# control-10.net
KiCad netlist of a schematic drawn in EAGLE
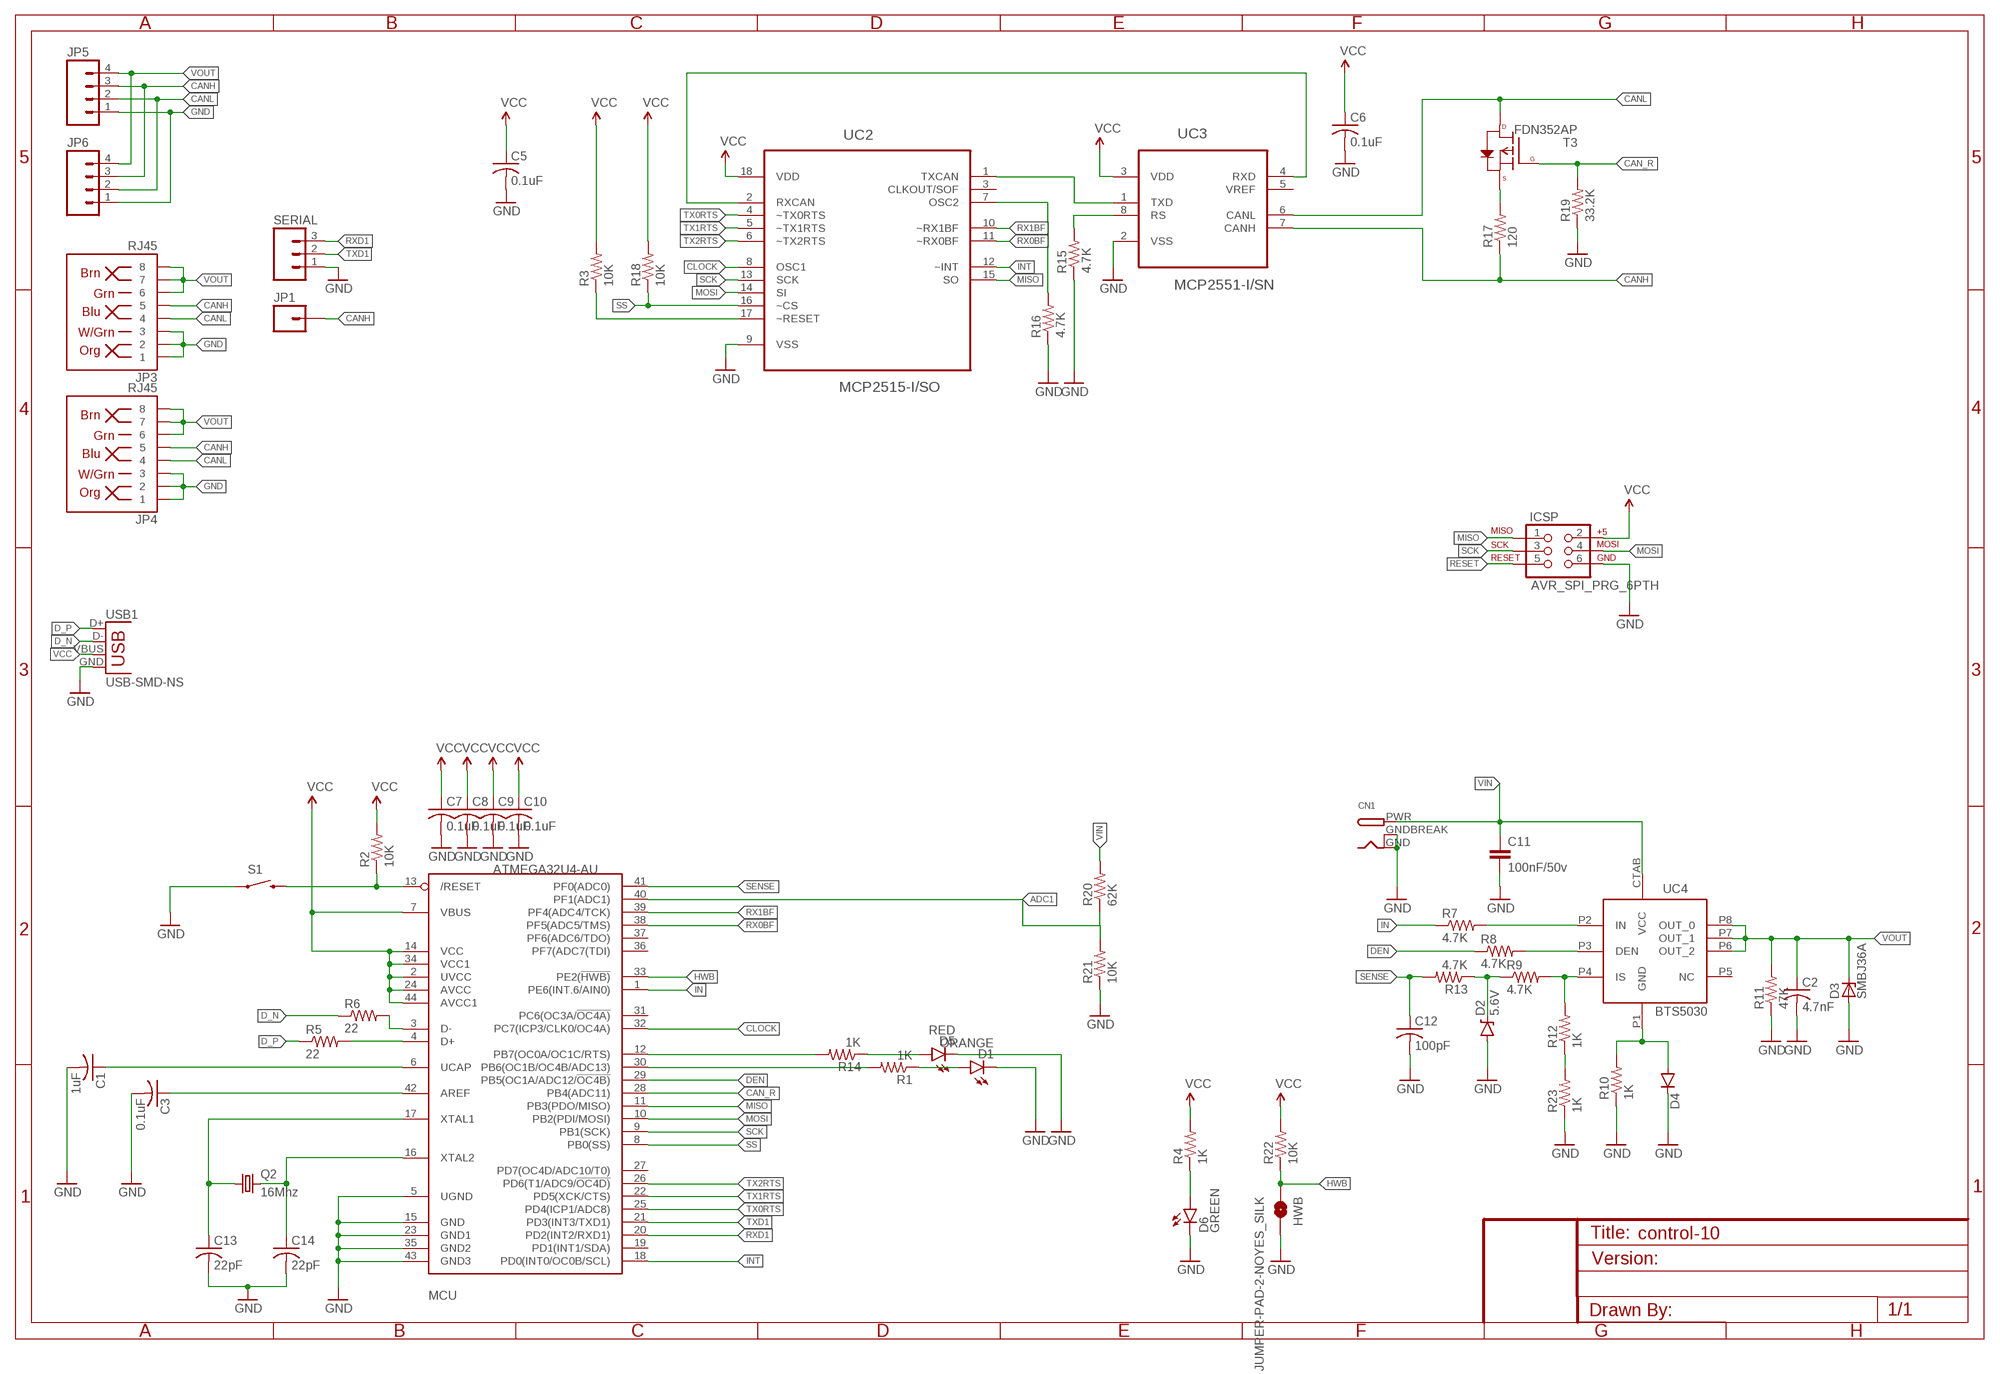
[diagram p0: schematic, sheet 1]

(export (version "E")
  (design (tool "Eeschema 10.0.6"))
  (components
    (comp (ref "C1")
      (value "1uF")
      (footprint "eagle-import:C0805")
      (libsource (lib "eagle-import") (part "C-USC0805"))
    )
    (comp (ref "C2")
      (value "4.7nF")
      (footprint "eagle-import:C0805")
      (libsource (lib "eagle-import") (part "C-USC0805"))
    )
    (comp (ref "C3")
      (value "0.1uF")
      (footprint "eagle-import:C0603")
      (libsource (lib "eagle-import") (part "C-USC0603"))
    )
    (comp (ref "C5")
      (value "0.1uF")
      (footprint "eagle-import:C0603")
      (libsource (lib "eagle-import") (part "C-USC0603"))
    )
    (comp (ref "C6")
      (value "0.1uF")
      (footprint "eagle-import:C0603")
      (libsource (lib "eagle-import") (part "C-USC0603"))
    )
    (comp (ref "C7")
      (value "0.1uF")
      (footprint "eagle-import:C0603")
      (libsource (lib "eagle-import") (part "C-USC0603"))
    )
    (comp (ref "C8")
      (value "0.1uF")
      (footprint "eagle-import:C0603")
      (libsource (lib "eagle-import") (part "C-USC0603"))
    )
    (comp (ref "C9")
      (value "0.1uF")
      (footprint "eagle-import:C0603")
      (libsource (lib "eagle-import") (part "C-USC0603"))
    )
    (comp (ref "C10")
      (value "0.1uF")
      (footprint "eagle-import:C0603")
      (libsource (lib "eagle-import") (part "C-USC0603"))
    )
    (comp (ref "C11")
      (value "100nF/50v")
      (footprint "eagle-import:0805")
      (libsource (lib "eagle-import") (part "CAP0805"))
    )
    (comp (ref "C12")
      (value "100pF")
      (footprint "eagle-import:C0805")
      (libsource (lib "eagle-import") (part "C-USC0805"))
    )
    (comp (ref "C13")
      (value "22pF")
      (footprint "eagle-import:C0805")
      (libsource (lib "eagle-import") (part "C-USC0805"))
    )
    (comp (ref "C14")
      (value "22pF")
      (footprint "eagle-import:C0805")
      (libsource (lib "eagle-import") (part "C-USC0805"))
    )
    (comp (ref "CN1")
      (value "DCBARRELPTH")
      (footprint "eagle-import:DCJACK_2MM_PTH")
      (libsource (lib "eagle-import") (part "DCBARRELPTH"))
    )
    (comp (ref "D1")
      (value "ORANGE")
      (footprint "eagle-import:LED-1206")
      (libsource (lib "eagle-import") (part "LED1206"))
    )
    (comp (ref "D2")
      (value "5.6V")
      (footprint "eagle-import:SOD-323")
      (libsource (lib "eagle-import") (part "DIODE-ZENER5.6V"))
    )
    (comp (ref "D3")
      (value "SMBJ36A")
      (footprint "eagle-import:SMB")
      (libsource (lib "eagle-import") (part "ZENER-DIODESMB"))
    )
    (comp (ref "D4")
      (value "DIODESMA")
      (footprint "eagle-import:SMA-DIODE")
      (libsource (lib "eagle-import") (part "DIODESMA"))
    )
    (comp (ref "D5")
      (value "RED")
      (footprint "eagle-import:LED-1206")
      (libsource (lib "eagle-import") (part "LED1206"))
    )
    (comp (ref "D6")
      (value "GREEN")
      (footprint "eagle-import:LED-1206")
      (libsource (lib "eagle-import") (part "LED1206"))
    )
    (comp (ref "HWB")
      (value "JUMPER-PAD-2-NOYES_SILK")
      (footprint "eagle-import:PAD-JUMPER-2-NO_YES_SILK")
      (libsource (lib "eagle-import") (part "JUMPER-PAD-2-NOYES_SILK"))
    )
    (comp (ref "ICSP")
      (value "AVR_SPI_PRG_6PTH")
      (footprint "eagle-import:2X3")
      (libsource (lib "eagle-import") (part "AVR_SPI_PRG_6PTH"))
    )
    (comp (ref "JP1")
      (value "M01NOSILK-KIT")
      (footprint "eagle-import:1X01NS-KIT")
      (libsource (lib "eagle-import") (part "M01NOSILK-KIT"))
    )
    (comp (ref "JP3")
      (value "RJ45")
      (footprint "eagle-import:RJ45-8")
      (libsource (lib "eagle-import") (part "RJ45-8PTH"))
    )
    (comp (ref "JP4")
      (value "RJ45")
      (footprint "eagle-import:RJ45-8")
      (libsource (lib "eagle-import") (part "RJ45-8PTH"))
    )
    (comp (ref "JP5")
      (value "M04SCREW")
      (footprint "eagle-import:SCREWTERMINAL-3.5MM-4")
      (libsource (lib "eagle-import") (part "M04SCREW"))
    )
    (comp (ref "JP6")
      (value "M04SCREW")
      (footprint "eagle-import:SCREWTERMINAL-3.5MM-4")
      (libsource (lib "eagle-import") (part "M04SCREW"))
    )
    (comp (ref "MCU")
      (value "ATMEGA32U4-AU")
      (footprint "eagle-import:TQFP44")
      (libsource (lib "eagle-import") (part "ATMEGA32U4-AU"))
    )
    (comp (ref "Q2")
      (value "16Mhz")
      (footprint "eagle-import:HC49UP")
      (libsource (lib "eagle-import") (part "CRYSTALSMD"))
    )
    (comp (ref "R1")
      (value "1K")
      (footprint "eagle-import:0805")
      (libsource (lib "eagle-import") (part "RESISTOR0805-RES"))
    )
    (comp (ref "R2")
      (value "10K")
      (footprint "eagle-import:M0805")
      (libsource (lib "eagle-import") (part "R-US_M0805"))
    )
    (comp (ref "R3")
      (value "10K")
      (footprint "eagle-import:M0805")
      (libsource (lib "eagle-import") (part "R-US_M0805"))
    )
    (comp (ref "R4")
      (value "1K")
      (footprint "eagle-import:0805")
      (libsource (lib "eagle-import") (part "RESISTOR0805-RES"))
    )
    (comp (ref "R5")
      (value "22")
      (footprint "eagle-import:M0805")
      (libsource (lib "eagle-import") (part "R-US_M0805"))
    )
    (comp (ref "R6")
      (value "22")
      (footprint "eagle-import:M0805")
      (libsource (lib "eagle-import") (part "R-US_M0805"))
    )
    (comp (ref "R7")
      (value "4.7K")
      (footprint "eagle-import:M0805")
      (libsource (lib "eagle-import") (part "R-US_M0805"))
    )
    (comp (ref "R8")
      (value "4.7K")
      (footprint "eagle-import:M0805")
      (libsource (lib "eagle-import") (part "R-US_M0805"))
    )
    (comp (ref "R9")
      (value "4.7K")
      (footprint "eagle-import:M0805")
      (libsource (lib "eagle-import") (part "R-US_M0805"))
    )
    (comp (ref "R10")
      (value "1K")
      (footprint "eagle-import:M0805")
      (libsource (lib "eagle-import") (part "R-US_M0805"))
    )
    (comp (ref "R11")
      (value "47K")
      (footprint "eagle-import:M0805")
      (libsource (lib "eagle-import") (part "R-US_M0805"))
    )
    (comp (ref "R12")
      (value "1K")
      (footprint "eagle-import:M0805")
      (libsource (lib "eagle-import") (part "R-US_M0805"))
    )
    (comp (ref "R13")
      (value "4.7K")
      (footprint "eagle-import:M0805")
      (libsource (lib "eagle-import") (part "R-US_M0805"))
    )
    (comp (ref "R14")
      (value "1K")
      (footprint "eagle-import:0805")
      (libsource (lib "eagle-import") (part "RESISTOR0805-RES"))
    )
    (comp (ref "R15")
      (value "4.7K")
      (footprint "eagle-import:M0805")
      (libsource (lib "eagle-import") (part "R-US_M0805"))
    )
    (comp (ref "R16")
      (value "4.7K")
      (footprint "eagle-import:M0805")
      (libsource (lib "eagle-import") (part "R-US_M0805"))
    )
    (comp (ref "R17")
      (value "120")
      (footprint "eagle-import:M0805")
      (libsource (lib "eagle-import") (part "R-US_M0805"))
    )
    (comp (ref "R18")
      (value "10K")
      (footprint "eagle-import:M0805")
      (libsource (lib "eagle-import") (part "R-US_M0805"))
    )
    (comp (ref "R19")
      (value "33.2K")
      (footprint "eagle-import:M0805")
      (libsource (lib "eagle-import") (part "R-US_M0805"))
    )
    (comp (ref "R20")
      (value "62K")
      (footprint "eagle-import:M0805")
      (libsource (lib "eagle-import") (part "R-US_M0805"))
    )
    (comp (ref "R21")
      (value "10K")
      (footprint "eagle-import:M0805")
      (libsource (lib "eagle-import") (part "R-US_M0805"))
    )
    (comp (ref "R22")
      (value "10K")
      (footprint "eagle-import:M0805")
      (libsource (lib "eagle-import") (part "R-US_M0805"))
    )
    (comp (ref "R23")
      (value "1K")
      (footprint "eagle-import:M0805")
      (libsource (lib "eagle-import") (part "R-US_M0805"))
    )
    (comp (ref "S1")
      (value "SWITCH-MOMENTARY-2SMD-1101NE")
      (footprint "eagle-import:TACTILE-SWITCH-1101NE")
      (libsource (lib "eagle-import") (part "SWITCH-MOMENTARY-2SMD-1101NE"))
    )
    (comp (ref "SERIAL")
      (value "M03PTH")
      (footprint "eagle-import:1X03")
      (libsource (lib "eagle-import") (part "M03PTH"))
    )
    (comp (ref "T3")
      (value "FDN352AP")
      (footprint "eagle-import:SOT23-3")
      (libsource (lib "eagle-import") (part "P-CHANNEL-MOSFET"))
    )
    (comp (ref "UC2")
      (value "MCP2515-I/SO")
      (footprint "eagle-import:SOIC127P1034X264-18N")
      (libsource (lib "eagle-import") (part "MCP2515-I/SO"))
    )
    (comp (ref "UC3")
      (value "MCP2551-I/SN")
      (footprint "eagle-import:SOIC127P600X175-8N")
      (libsource (lib "eagle-import") (part "MCP2551-I/SN"))
    )
    (comp (ref "UC4")
      (value "BTS5030")
      (footprint "eagle-import:PG-DSO-8-43")
      (libsource (lib "eagle-import") (part "BTS5030"))
    )
    (comp (ref "USB1")
      (value "USB-SMD-NS")
      (footprint "eagle-import:USB-MINIB-NOSTOP")
      (libsource (lib "eagle-import") (part "USB-SMD-NS"))
    )
  )
  (nets
    (net (code "1") (name "ADC1") (class "Default")
      (node (ref "MCU") (pin "40") (pinfunction "PF1(ADC1)_40") (pintype "bidirectional"))
      (node (ref "R20") (pin "1") (pinfunction "1_1") (pintype "passive"))
      (node (ref "R21") (pin "2") (pinfunction "2_2") (pintype "passive"))
    )
    (net (code "2") (name "CANH") (class "Default")
      (node (ref "JP1") (pin "1") (pinfunction "1_1") (pintype "passive"))
      (node (ref "JP3") (pin "5") (pinfunction "5_5") (pintype "bidirectional"))
      (node (ref "JP4") (pin "5") (pinfunction "5_5") (pintype "bidirectional"))
      (node (ref "JP5") (pin "3") (pinfunction "3_3") (pintype "passive"))
      (node (ref "JP6") (pin "3") (pinfunction "3_3") (pintype "passive"))
      (node (ref "R17") (pin "1") (pinfunction "1_1") (pintype "passive"))
      (node (ref "UC3") (pin "7") (pinfunction "CANH_7") (pintype "bidirectional"))
    )
    (net (code "3") (name "CANL") (class "Default")
      (node (ref "JP3") (pin "4") (pinfunction "4_4") (pintype "bidirectional"))
      (node (ref "JP4") (pin "4") (pinfunction "4_4") (pintype "bidirectional"))
      (node (ref "JP5") (pin "2") (pinfunction "2_2") (pintype "passive"))
      (node (ref "JP6") (pin "2") (pinfunction "2_2") (pintype "passive"))
      (node (ref "T3") (pin "3") (pinfunction "D_3") (pintype "passive"))
      (node (ref "UC3") (pin "6") (pinfunction "CANL_6") (pintype "bidirectional"))
    )
    (net (code "4") (name "CAN_R") (class "Default")
      (node (ref "MCU") (pin "28") (pinfunction "PB4(ADC11)_28") (pintype "bidirectional"))
      (node (ref "R19") (pin "2") (pinfunction "2_2") (pintype "passive"))
      (node (ref "T3") (pin "1") (pinfunction "G_1") (pintype "passive"))
    )
    (net (code "5") (name "CLOCK") (class "Default")
      (node (ref "MCU") (pin "32") (pinfunction "PC7(ICP3/CLK0/OC4A)_32") (pintype "bidirectional"))
      (node (ref "UC2") (pin "8") (pinfunction "OSC1_8") (pintype "input"))
    )
    (net (code "6") (name "DEN") (class "Default")
      (node (ref "MCU") (pin "29") (pinfunction "PB5(OC1A/ADC12/~{OC4B})_29") (pintype "bidirectional"))
      (node (ref "R8") (pin "1") (pinfunction "1_1") (pintype "passive"))
    )
    (net (code "7") (name "D_N") (class "Default")
      (node (ref "R6") (pin "1") (pinfunction "1_1") (pintype "passive"))
      (node (ref "USB1") (pin "D-") (pinfunction "D-_D-") (pintype "bidirectional"))
    )
    (net (code "8") (name "D_P") (class "Default")
      (node (ref "R5") (pin "1") (pinfunction "1_1") (pintype "passive"))
      (node (ref "USB1") (pin "D+") (pinfunction "D+_D+") (pintype "bidirectional"))
    )
    (net (code "9") (name "GND") (class "Default")
      (node (ref "C1") (pin "2") (pinfunction "2_2") (pintype "passive"))
      (node (ref "C10") (pin "2") (pinfunction "2_2") (pintype "passive"))
      (node (ref "C11") (pin "2") (pinfunction "2_2") (pintype "passive"))
      (node (ref "C12") (pin "2") (pinfunction "2_2") (pintype "passive"))
      (node (ref "C13") (pin "2") (pinfunction "2_2") (pintype "passive"))
      (node (ref "C14") (pin "2") (pinfunction "2_2") (pintype "passive"))
      (node (ref "C2") (pin "2") (pinfunction "2_2") (pintype "passive"))
      (node (ref "C3") (pin "2") (pinfunction "2_2") (pintype "passive"))
      (node (ref "C5") (pin "2") (pinfunction "2_2") (pintype "passive"))
      (node (ref "C6") (pin "2") (pinfunction "2_2") (pintype "passive"))
      (node (ref "C7") (pin "2") (pinfunction "2_2") (pintype "passive"))
      (node (ref "C8") (pin "2") (pinfunction "2_2") (pintype "passive"))
      (node (ref "C9") (pin "2") (pinfunction "2_2") (pintype "passive"))
      (node (ref "CN1") (pin "GND") (pinfunction "GND_GND") (pintype "power_in"))
      (node (ref "CN1") (pin "GNDBREAK") (pinfunction "GNDBREAK_GNDBREAK") (pintype "power_in"))
      (node (ref "D1") (pin "C") (pinfunction "C_C") (pintype "passive"))
      (node (ref "D2") (pin "A") (pinfunction "A_A") (pintype "passive"))
      (node (ref "D3") (pin "A") (pinfunction "A_A") (pintype "passive"))
      (node (ref "D4") (pin "C") (pinfunction "C_C") (pintype "passive"))
      (node (ref "D5") (pin "C") (pinfunction "C_C") (pintype "passive"))
      (node (ref "D6") (pin "C") (pinfunction "C_C") (pintype "passive"))
      (node (ref "HWB") (pin "2") (pinfunction "2_2") (pintype "passive"))
      (node (ref "ICSP") (pin "6") (pinfunction "6_6") (pintype "passive"))
      (node (ref "JP3") (pin "1") (pinfunction "1_1") (pintype "bidirectional"))
      (node (ref "JP3") (pin "2") (pinfunction "2_2") (pintype "bidirectional"))
      (node (ref "JP3") (pin "3") (pinfunction "3_3") (pintype "bidirectional"))
      (node (ref "JP4") (pin "1") (pinfunction "1_1") (pintype "bidirectional"))
      (node (ref "JP4") (pin "2") (pinfunction "2_2") (pintype "bidirectional"))
      (node (ref "JP4") (pin "3") (pinfunction "3_3") (pintype "bidirectional"))
      (node (ref "JP5") (pin "1") (pinfunction "1_1") (pintype "passive"))
      (node (ref "JP6") (pin "1") (pinfunction "1_1") (pintype "passive"))
      (node (ref "MCU") (pin "15") (pinfunction "GND_15") (pintype "bidirectional"))
      (node (ref "MCU") (pin "23") (pinfunction "GND1_23") (pintype "bidirectional"))
      (node (ref "MCU") (pin "35") (pinfunction "GND2_35") (pintype "bidirectional"))
      (node (ref "MCU") (pin "43") (pinfunction "GND3_43") (pintype "bidirectional"))
      (node (ref "MCU") (pin "5") (pinfunction "UGND_5") (pintype "bidirectional"))
      (node (ref "R10") (pin "1") (pinfunction "1_1") (pintype "passive"))
      (node (ref "R11") (pin "1") (pinfunction "1_1") (pintype "passive"))
      (node (ref "R15") (pin "1") (pinfunction "1_1") (pintype "passive"))
      (node (ref "R16") (pin "1") (pinfunction "1_1") (pintype "passive"))
      (node (ref "R19") (pin "1") (pinfunction "1_1") (pintype "passive"))
      (node (ref "R21") (pin "1") (pinfunction "1_1") (pintype "passive"))
      (node (ref "R23") (pin "1") (pinfunction "1_1") (pintype "passive"))
      (node (ref "S1") (pin "1") (pinfunction "1_1") (pintype "passive"))
      (node (ref "SERIAL") (pin "1") (pinfunction "1_1") (pintype "passive"))
      (node (ref "UC2") (pin "9") (pinfunction "VSS_9") (pintype "power_in"))
      (node (ref "UC3") (pin "2") (pinfunction "VSS_2") (pintype "passive"))
      (node (ref "USB1") (pin "GND") (pinfunction "GND_GND") (pintype "bidirectional"))
    )
    (net (code "10") (name "HWB") (class "Default")
      (node (ref "HWB") (pin "1") (pinfunction "1_1") (pintype "passive"))
      (node (ref "MCU") (pin "33") (pinfunction "PE2(~{HWB})_33") (pintype "bidirectional"))
      (node (ref "R22") (pin "1") (pinfunction "1_1") (pintype "passive"))
    )
    (net (code "11") (name "IN") (class "Default")
      (node (ref "MCU") (pin "1") (pinfunction "PE6(INT.6/AIN0)_1") (pintype "bidirectional"))
      (node (ref "R7") (pin "1") (pinfunction "1_1") (pintype "passive"))
    )
    (net (code "12") (name "INT") (class "Default")
      (node (ref "MCU") (pin "18") (pinfunction "PD0(INT0/OC0B/SCL)_18") (pintype "bidirectional"))
      (node (ref "UC2") (pin "12") (pinfunction "~{INT}_12") (pintype "output"))
    )
    (net (code "13") (name "MISO") (class "Default")
      (node (ref "ICSP") (pin "1") (pinfunction "1_1") (pintype "passive"))
      (node (ref "MCU") (pin "11") (pinfunction "PB3(PDO/MISO)_11") (pintype "bidirectional"))
      (node (ref "UC2") (pin "15") (pinfunction "SO_15") (pintype "output"))
    )
    (net (code "14") (name "MOSI") (class "Default")
      (node (ref "ICSP") (pin "4") (pinfunction "4_4") (pintype "passive"))
      (node (ref "MCU") (pin "10") (pinfunction "PB2(PDI/MOSI)_10") (pintype "bidirectional"))
      (node (ref "UC2") (pin "14") (pinfunction "SI_14") (pintype "input"))
    )
    (net (code "15") (name "Net-(D1-PadA)") (class "Default")
      (node (ref "D1") (pin "A") (pinfunction "A_A") (pintype "passive"))
      (node (ref "R1") (pin "1") (pinfunction "1_1") (pintype "passive"))
    )
    (net (code "16") (name "Net-(D2-PadC)") (class "Default")
      (node (ref "D2") (pin "C") (pinfunction "C_C") (pintype "passive"))
      (node (ref "R13") (pin "1") (pinfunction "1_1") (pintype "passive"))
      (node (ref "R9") (pin "1") (pinfunction "1_1") (pintype "passive"))
    )
    (net (code "17") (name "Net-(D5-PadA)") (class "Default")
      (node (ref "D5") (pin "A") (pinfunction "A_A") (pintype "passive"))
      (node (ref "R14") (pin "1") (pinfunction "1_1") (pintype "passive"))
    )
    (net (code "18") (name "Net-(D6-PadA)") (class "Default")
      (node (ref "D6") (pin "A") (pinfunction "A_A") (pintype "passive"))
      (node (ref "R4") (pin "1") (pinfunction "1_1") (pintype "passive"))
    )
    (net (code "19") (name "Net-(MCU-AREF)") (class "Default")
      (node (ref "C3") (pin "1") (pinfunction "1_1") (pintype "passive"))
      (node (ref "MCU") (pin "42") (pinfunction "AREF_42") (pintype "bidirectional"))
    )
    (net (code "20") (name "Net-(MCU-D+)") (class "Default")
      (node (ref "MCU") (pin "4") (pinfunction "D+_4") (pintype "bidirectional"))
      (node (ref "R5") (pin "2") (pinfunction "2_2") (pintype "passive"))
    )
    (net (code "21") (name "Net-(MCU-D-)") (class "Default")
      (node (ref "MCU") (pin "3") (pinfunction "D-_3") (pintype "bidirectional"))
      (node (ref "R6") (pin "2") (pinfunction "2_2") (pintype "passive"))
    )
    (net (code "22") (name "Net-(MCU-PB6(OC1B{slash}OC4B{slash}ADC13))") (class "Default")
      (node (ref "MCU") (pin "30") (pinfunction "PB6(OC1B/OC4B/ADC13)_30") (pintype "bidirectional"))
      (node (ref "R1") (pin "2") (pinfunction "2_2") (pintype "passive"))
    )
    (net (code "23") (name "Net-(MCU-PB7(OC0A{slash}OC1C{slash}RTS))") (class "Default")
      (node (ref "MCU") (pin "12") (pinfunction "PB7(OC0A/OC1C/RTS)_12") (pintype "bidirectional"))
      (node (ref "R14") (pin "2") (pinfunction "2_2") (pintype "passive"))
    )
    (net (code "24") (name "Net-(MCU-UCAP)") (class "Default")
      (node (ref "C1") (pin "1") (pinfunction "1_1") (pintype "passive"))
      (node (ref "MCU") (pin "6") (pinfunction "UCAP_6") (pintype "bidirectional"))
    )
    (net (code "25") (name "Net-(MCU-XTAL1)") (class "Default")
      (node (ref "C13") (pin "1") (pinfunction "1_1") (pintype "passive"))
      (node (ref "MCU") (pin "17") (pinfunction "XTAL1_17") (pintype "bidirectional"))
      (node (ref "Q2") (pin "1") (pinfunction "1_1") (pintype "passive"))
    )
    (net (code "26") (name "Net-(MCU-XTAL2)") (class "Default")
      (node (ref "C14") (pin "1") (pinfunction "1_1") (pintype "passive"))
      (node (ref "MCU") (pin "16") (pinfunction "XTAL2_16") (pintype "bidirectional"))
      (node (ref "Q2") (pin "2") (pinfunction "2_2") (pintype "passive"))
    )
    (net (code "27") (name "Net-(R12-Pad1)") (class "Default")
      (node (ref "R12") (pin "1") (pinfunction "1_1") (pintype "passive"))
      (node (ref "R23") (pin "2") (pinfunction "2_2") (pintype "passive"))
    )
    (net (code "28") (name "Net-(T3-S)") (class "Default")
      (node (ref "R17") (pin "2") (pinfunction "2_2") (pintype "passive"))
      (node (ref "T3") (pin "2") (pinfunction "S_2") (pintype "passive"))
    )
    (net (code "29") (name "Net-(UC2-OSC2)") (class "Default")
      (node (ref "R16") (pin "2") (pinfunction "2_2") (pintype "passive"))
      (node (ref "UC2") (pin "7") (pinfunction "OSC2_7") (pintype "output"))
    )
    (net (code "30") (name "Net-(UC2-RXCAN)") (class "Default")
      (node (ref "UC2") (pin "2") (pinfunction "RXCAN_2") (pintype "input"))
      (node (ref "UC3") (pin "4") (pinfunction "RXD_4") (pintype "output"))
    )
    (net (code "31") (name "Net-(UC2-TXCAN)") (class "Default")
      (node (ref "UC2") (pin "1") (pinfunction "TXCAN_1") (pintype "output"))
      (node (ref "UC3") (pin "1") (pinfunction "TXD_1") (pintype "input"))
    )
    (net (code "32") (name "Net-(UC2-~{RESET})") (class "Default")
      (node (ref "R3") (pin "1") (pinfunction "1_1") (pintype "passive"))
      (node (ref "UC2") (pin "17") (pinfunction "~{RESET}_17") (pintype "input"))
    )
    (net (code "33") (name "Net-(UC3-RS)") (class "Default")
      (node (ref "R15") (pin "2") (pinfunction "2_2") (pintype "passive"))
      (node (ref "UC3") (pin "8") (pinfunction "RS_8") (pintype "input"))
    )
    (net (code "34") (name "Net-(UC4-DEN)") (class "Default")
      (node (ref "R8") (pin "2") (pinfunction "2_2") (pintype "passive"))
      (node (ref "UC4") (pin "P3") (pinfunction "DEN_P3") (pintype "bidirectional"))
    )
    (net (code "35") (name "Net-(UC4-GND)") (class "Default")
      (node (ref "D4") (pin "A") (pinfunction "A_A") (pintype "passive"))
      (node (ref "R10") (pin "2") (pinfunction "2_2") (pintype "passive"))
      (node (ref "UC4") (pin "P1") (pinfunction "GND_P1") (pintype "bidirectional"))
    )
    (net (code "36") (name "Net-(UC4-IN)") (class "Default")
      (node (ref "R7") (pin "2") (pinfunction "2_2") (pintype "passive"))
      (node (ref "UC4") (pin "P2") (pinfunction "IN_P2") (pintype "bidirectional"))
    )
    (net (code "37") (name "Net-(UC4-IS)") (class "Default")
      (node (ref "R12") (pin "2") (pinfunction "2_2") (pintype "passive"))
      (node (ref "R9") (pin "2") (pinfunction "2_2") (pintype "passive"))
      (node (ref "UC4") (pin "P4") (pinfunction "IS_P4") (pintype "bidirectional"))
    )
    (net (code "38") (name "RESET") (class "Default")
      (node (ref "ICSP") (pin "5") (pinfunction "5_5") (pintype "passive"))
      (node (ref "MCU") (pin "13") (pinfunction "/RESET_13") (pintype "bidirectional"))
      (node (ref "R2") (pin "1") (pinfunction "1_1") (pintype "passive"))
      (node (ref "S1") (pin "2") (pinfunction "2_2") (pintype "passive"))
    )
    (net (code "39") (name "RX0BF") (class "Default")
      (node (ref "MCU") (pin "38") (pinfunction "PF5(ADC5/TMS)_38") (pintype "bidirectional"))
      (node (ref "UC2") (pin "11") (pinfunction "~{RX0BF}_11") (pintype "output"))
    )
    (net (code "40") (name "RX1BF") (class "Default")
      (node (ref "MCU") (pin "39") (pinfunction "PF4(ADC4/TCK)_39") (pintype "bidirectional"))
      (node (ref "UC2") (pin "10") (pinfunction "~{RX1BF}_10") (pintype "output"))
    )
    (net (code "41") (name "RXD1") (class "Default")
      (node (ref "MCU") (pin "20") (pinfunction "PD2(INT2/RXD1)_20") (pintype "bidirectional"))
      (node (ref "SERIAL") (pin "3") (pinfunction "3_3") (pintype "passive"))
    )
    (net (code "42") (name "SCK") (class "Default")
      (node (ref "ICSP") (pin "3") (pinfunction "3_3") (pintype "passive"))
      (node (ref "MCU") (pin "9") (pinfunction "PB1(SCK)_9") (pintype "bidirectional"))
      (node (ref "UC2") (pin "13") (pinfunction "SCK_13") (pintype "input"))
    )
    (net (code "43") (name "SENSE") (class "Default")
      (node (ref "C12") (pin "1") (pinfunction "1_1") (pintype "passive"))
      (node (ref "MCU") (pin "41") (pinfunction "PF0(ADC0)_41") (pintype "bidirectional"))
      (node (ref "R13") (pin "2") (pinfunction "2_2") (pintype "passive"))
    )
    (net (code "44") (name "SS") (class "Default")
      (node (ref "MCU") (pin "8") (pinfunction "PB0(SS)_8") (pintype "bidirectional"))
      (node (ref "R18") (pin "1") (pinfunction "1_1") (pintype "passive"))
      (node (ref "UC2") (pin "16") (pinfunction "~{CS}_16") (pintype "input"))
    )
    (net (code "45") (name "TX0RTS") (class "Default")
      (node (ref "MCU") (pin "25") (pinfunction "PD4(ICP1/ADC8)_25") (pintype "bidirectional"))
      (node (ref "UC2") (pin "4") (pinfunction "~{TX0RTS}_4") (pintype "input"))
    )
    (net (code "46") (name "TX1RTS") (class "Default")
      (node (ref "MCU") (pin "22") (pinfunction "PD5(XCK/CTS)_22") (pintype "bidirectional"))
      (node (ref "UC2") (pin "5") (pinfunction "~{TX1RTS}_5") (pintype "input"))
    )
    (net (code "47") (name "TX2RTS") (class "Default")
      (node (ref "MCU") (pin "26") (pinfunction "PD6(T1/ADC9/~{OC4D})_26") (pintype "bidirectional"))
      (node (ref "UC2") (pin "6") (pinfunction "~{TX2RTS}_6") (pintype "input"))
    )
    (net (code "48") (name "TXD1") (class "Default")
      (node (ref "MCU") (pin "21") (pinfunction "PD3(INT3/TXD1)_21") (pintype "bidirectional"))
      (node (ref "SERIAL") (pin "2") (pinfunction "2_2") (pintype "passive"))
    )
    (net (code "49") (name "VCC") (class "Default")
      (node (ref "C10") (pin "1") (pinfunction "1_1") (pintype "passive"))
      (node (ref "C5") (pin "1") (pinfunction "1_1") (pintype "passive"))
      (node (ref "C6") (pin "1") (pinfunction "1_1") (pintype "passive"))
      (node (ref "C7") (pin "1") (pinfunction "1_1") (pintype "passive"))
      (node (ref "C8") (pin "1") (pinfunction "1_1") (pintype "passive"))
      (node (ref "C9") (pin "1") (pinfunction "1_1") (pintype "passive"))
      (node (ref "ICSP") (pin "2") (pinfunction "2_2") (pintype "passive"))
      (node (ref "MCU") (pin "14") (pinfunction "VCC_14") (pintype "bidirectional"))
      (node (ref "MCU") (pin "2") (pinfunction "UVCC_2") (pintype "bidirectional"))
      (node (ref "MCU") (pin "24") (pinfunction "AVCC_24") (pintype "bidirectional"))
      (node (ref "MCU") (pin "34") (pinfunction "VCC1_34") (pintype "bidirectional"))
      (node (ref "MCU") (pin "44") (pinfunction "AVCC1_44") (pintype "bidirectional"))
      (node (ref "MCU") (pin "7") (pinfunction "VBUS_7") (pintype "bidirectional"))
      (node (ref "R18") (pin "2") (pinfunction "2_2") (pintype "passive"))
      (node (ref "R2") (pin "2") (pinfunction "2_2") (pintype "passive"))
      (node (ref "R22") (pin "2") (pinfunction "2_2") (pintype "passive"))
      (node (ref "R3") (pin "2") (pinfunction "2_2") (pintype "passive"))
      (node (ref "R4") (pin "2") (pinfunction "2_2") (pintype "passive"))
      (node (ref "UC2") (pin "18") (pinfunction "VDD_18") (pintype "power_in"))
      (node (ref "UC3") (pin "3") (pinfunction "VDD_3") (pintype "power_in"))
      (node (ref "USB1") (pin "VBUS") (pinfunction "VBUS_VBUS") (pintype "bidirectional"))
    )
    (net (code "50") (name "VIN") (class "Default")
      (node (ref "C11") (pin "1") (pinfunction "1_1") (pintype "passive"))
      (node (ref "CN1") (pin "PWR") (pinfunction "PWR_PWR") (pintype "power_in"))
      (node (ref "R20") (pin "2") (pinfunction "2_2") (pintype "passive"))
      (node (ref "UC4") (pin "CTAB") (pinfunction "VCC_CTAB") (pintype "bidirectional"))
    )
    (net (code "51") (name "VOUT") (class "Default")
      (node (ref "C2") (pin "1") (pinfunction "1_1") (pintype "passive"))
      (node (ref "D3") (pin "C") (pinfunction "C_C") (pintype "passive"))
      (node (ref "JP3") (pin "6") (pinfunction "6_6") (pintype "bidirectional"))
      (node (ref "JP3") (pin "7") (pinfunction "7_7") (pintype "bidirectional"))
      (node (ref "JP3") (pin "8") (pinfunction "8_8") (pintype "bidirectional"))
      (node (ref "JP4") (pin "6") (pinfunction "6_6") (pintype "bidirectional"))
      (node (ref "JP4") (pin "7") (pinfunction "7_7") (pintype "bidirectional"))
      (node (ref "JP4") (pin "8") (pinfunction "8_8") (pintype "bidirectional"))
      (node (ref "JP5") (pin "4") (pinfunction "4_4") (pintype "passive"))
      (node (ref "JP6") (pin "4") (pinfunction "4_4") (pintype "passive"))
      (node (ref "R11") (pin "2") (pinfunction "2_2") (pintype "passive"))
      (node (ref "UC4") (pin "P6") (pinfunction "OUT_2_P6") (pintype "bidirectional"))
      (node (ref "UC4") (pin "P7") (pinfunction "OUT_1_P7") (pintype "bidirectional"))
      (node (ref "UC4") (pin "P8") (pinfunction "OUT_0_P8") (pintype "bidirectional"))
    )
    (net (code "52") (name "unconnected-(MCU-PC6(OC3A{slash}~{OC4A})-Pad31)") (class "Default")
      (node (ref "MCU") (pin "31") (pinfunction "PC6(OC3A/~{OC4A})_31") (pintype "bidirectional"))
    )
    (net (code "53") (name "unconnected-(MCU-PD1(INT1{slash}SDA)-Pad19)") (class "Default")
      (node (ref "MCU") (pin "19") (pinfunction "PD1(INT1/SDA)_19") (pintype "bidirectional"))
    )
    (net (code "54") (name "unconnected-(MCU-PD7(OC4D{slash}ADC10{slash}T0)-Pad27)") (class "Default")
      (node (ref "MCU") (pin "27") (pinfunction "PD7(OC4D/ADC10/T0)_27") (pintype "bidirectional"))
    )
    (net (code "55") (name "unconnected-(MCU-PF6(ADC6{slash}TDO)-Pad37)") (class "Default")
      (node (ref "MCU") (pin "37") (pinfunction "PF6(ADC6/TDO)_37") (pintype "bidirectional"))
    )
    (net (code "56") (name "unconnected-(MCU-PF7(ADC7(TDI)-Pad36)") (class "Default")
      (node (ref "MCU") (pin "36") (pinfunction "PF7(ADC7(TDI)_36") (pintype "bidirectional"))
    )
    (net (code "57") (name "unconnected-(UC2-CLKOUT{slash}SOF-Pad3)") (class "Default")
      (node (ref "UC2") (pin "3") (pinfunction "CLKOUT/SOF_3") (pintype "output"))
    )
    (net (code "58") (name "unconnected-(UC3-VREF-Pad5)") (class "Default")
      (node (ref "UC3") (pin "5") (pinfunction "VREF_5") (pintype "output"))
    )
    (net (code "59") (name "unconnected-(UC4-NC-PadP5)") (class "Default")
      (node (ref "UC4") (pin "P5") (pinfunction "NC_P5") (pintype "no_connect"))
    )
  )
)
